# NanOSD.net
KiCad netlist of a schematic drawn in EAGLE
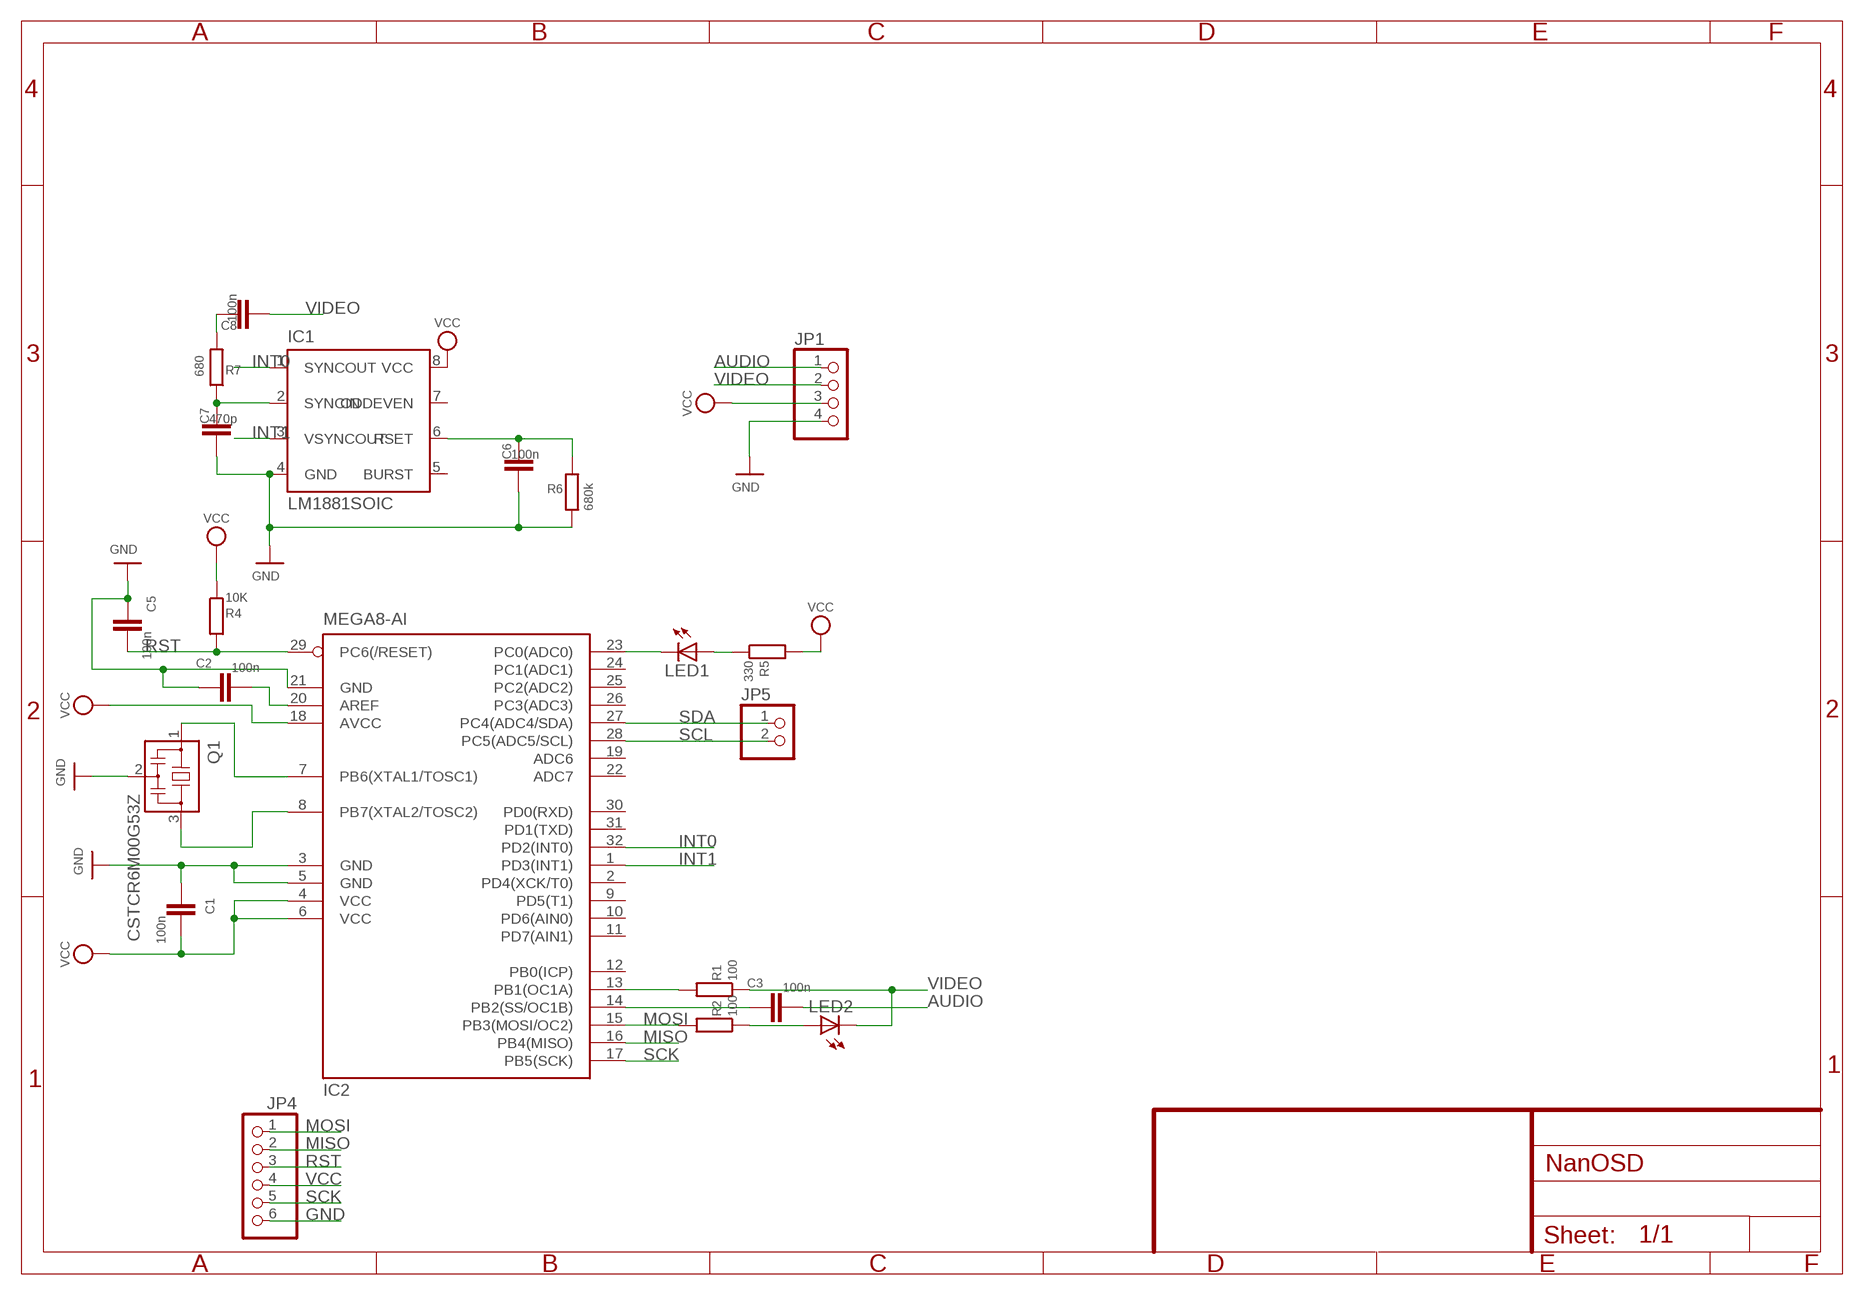
[diagram p0: schematic, sheet 1]

(export (version "E")
  (design (tool "Eeschema 10.0.6"))
  (components
    (comp (ref "C1")
      (value "100n")
      (footprint "eagle-import:C0805")
      (libsource (lib "eagle-import") (part "C-EUC0805"))
    )
    (comp (ref "C2")
      (value "100n")
      (footprint "eagle-import:C0805")
      (libsource (lib "eagle-import") (part "C-EUC0805"))
    )
    (comp (ref "C3")
      (value "100n")
      (footprint "eagle-import:C0805")
      (libsource (lib "eagle-import") (part "C-EUC0805"))
    )
    (comp (ref "C5")
      (value "100n")
      (footprint "eagle-import:C0805")
      (libsource (lib "eagle-import") (part "C-EUC0805"))
    )
    (comp (ref "C6")
      (value "100n")
      (footprint "eagle-import:C0805")
      (libsource (lib "eagle-import") (part "C-EUC0805"))
    )
    (comp (ref "C7")
      (value "470p")
      (footprint "eagle-import:C0805")
      (libsource (lib "eagle-import") (part "C-EUC0805"))
    )
    (comp (ref "C8")
      (value "100n")
      (footprint "eagle-import:C0805")
      (libsource (lib "eagle-import") (part "C-EUC0805"))
    )
    (comp (ref "IC1")
      (value "LM1881SOIC")
      (footprint "eagle-import:SO08")
      (libsource (lib "eagle-import") (part "LM1881SOIC"))
    )
    (comp (ref "IC2")
      (value "MEGA8-AI")
      (footprint "eagle-import:TQFP32-08")
      (fields (field (name "MPN") "ATMEGA8-16AU"))
      (libsource (lib "eagle-import") (part "MEGA8-AI"))
    )
    (comp (ref "JP1")
      (value "PINHD-1X4")
      (footprint "eagle-import:1X04")
      (libsource (lib "eagle-import") (part "PINHD-1X4"))
    )
    (comp (ref "JP4")
      (value "PINHD-1X61.27MM")
      (footprint "eagle-import:1X06")
      (libsource (lib "eagle-import") (part "PINHD-1X61.27MM"))
    )
    (comp (ref "JP5")
      (value "PINHD-1X2")
      (footprint "eagle-import:1X02")
      (libsource (lib "eagle-import") (part "PINHD-1X2"))
    )
    (comp (ref "LED1")
      (value "LEDCHIP-LED0805")
      (footprint "eagle-import:CHIP-LED0805")
      (libsource (lib "eagle-import") (part "LEDCHIP-LED0805"))
    )
    (comp (ref "LED2")
      (value "LEDCHIP-LED0805")
      (footprint "eagle-import:CHIP-LED0805")
      (libsource (lib "eagle-import") (part "LEDCHIP-LED0805"))
    )
    (comp (ref "Q1")
      (value "CSTCR6M00G53Z")
      (footprint "eagle-import:CSTCR6M")
      (fields (field (name "MPN") "CSTCR6M00G53-R0"))
      (libsource (lib "eagle-import") (part "CSTCR6M00G53Z"))
    )
    (comp (ref "R1")
      (value "100")
      (footprint "eagle-import:M0805")
      (libsource (lib "eagle-import") (part "R-EU_M0805"))
    )
    (comp (ref "R2")
      (value "100")
      (footprint "eagle-import:M0805")
      (libsource (lib "eagle-import") (part "R-EU_M0805"))
    )
    (comp (ref "R4")
      (value "10K")
      (footprint "eagle-import:M0805")
      (libsource (lib "eagle-import") (part "R-EU_M0805"))
    )
    (comp (ref "R5")
      (value "330")
      (footprint "eagle-import:M0805")
      (libsource (lib "eagle-import") (part "R-EU_M0805"))
    )
    (comp (ref "R6")
      (value "680k")
      (footprint "eagle-import:M0805")
      (libsource (lib "eagle-import") (part "R-EU_M0805"))
    )
    (comp (ref "R7")
      (value "680")
      (footprint "eagle-import:M0805")
      (libsource (lib "eagle-import") (part "R-EU_M0805"))
    )
  )
  (nets
    (net (code "1") (name "/AUDIO") (class "Default")
      (node (ref "C3") (pin "2") (pinfunction "2_2") (pintype "passive"))
      (node (ref "JP1") (pin "1") (pinfunction "1_1") (pintype "passive"))
    )
    (net (code "2") (name "/INT0") (class "Default")
      (node (ref "IC1") (pin "1") (pinfunction "SYNCOUT_1") (pintype "output"))
      (node (ref "IC2") (pin "32") (pinfunction "PD2(INT0)_32") (pintype "bidirectional"))
    )
    (net (code "3") (name "/INT1") (class "Default")
      (node (ref "IC1") (pin "3") (pinfunction "VSYNCOUT_3") (pintype "output"))
      (node (ref "IC2") (pin "1") (pinfunction "PD3(INT1)_1") (pintype "bidirectional"))
    )
    (net (code "4") (name "/MISO") (class "Default")
      (node (ref "IC2") (pin "16") (pinfunction "PB4(MISO)_16") (pintype "bidirectional"))
      (node (ref "JP4") (pin "2") (pinfunction "2_2") (pintype "passive"))
    )
    (net (code "5") (name "/MOSI") (class "Default")
      (node (ref "IC2") (pin "15") (pinfunction "PB3(MOSI/OC2)_15") (pintype "bidirectional"))
      (node (ref "JP4") (pin "1") (pinfunction "1_1") (pintype "passive"))
      (node (ref "R2") (pin "2") (pinfunction "2_2") (pintype "passive"))
    )
    (net (code "6") (name "/RST") (class "Default")
      (node (ref "C5") (pin "2") (pinfunction "2_2") (pintype "passive"))
      (node (ref "IC2") (pin "29") (pinfunction "PC6(/RESET)_29") (pintype "bidirectional"))
      (node (ref "JP4") (pin "3") (pinfunction "3_3") (pintype "passive"))
      (node (ref "R4") (pin "2") (pinfunction "2_2") (pintype "passive"))
    )
    (net (code "7") (name "/SCK") (class "Default")
      (node (ref "IC2") (pin "17") (pinfunction "PB5(SCK)_17") (pintype "bidirectional"))
      (node (ref "JP4") (pin "5") (pinfunction "5_5") (pintype "passive"))
    )
    (net (code "8") (name "/SCL") (class "Default")
      (node (ref "IC2") (pin "28") (pinfunction "PC5(ADC5/SCL)_28") (pintype "bidirectional"))
      (node (ref "JP5") (pin "2") (pinfunction "2_2") (pintype "passive"))
    )
    (net (code "9") (name "/SDA") (class "Default")
      (node (ref "IC2") (pin "27") (pinfunction "PC4(ADC4/SDA)_27") (pintype "bidirectional"))
      (node (ref "JP5") (pin "1") (pinfunction "1_1") (pintype "passive"))
    )
    (net (code "10") (name "/VIDEO") (class "Default")
      (node (ref "C8") (pin "1") (pinfunction "1_1") (pintype "passive"))
      (node (ref "JP1") (pin "2") (pinfunction "2_2") (pintype "passive"))
      (node (ref "LED2") (pin "C") (pinfunction "C_C") (pintype "passive"))
      (node (ref "R1") (pin "1") (pinfunction "1_1") (pintype "passive"))
    )
    (net (code "11") (name "GND") (class "Default")
      (node (ref "C1") (pin "1") (pinfunction "1_1") (pintype "passive"))
      (node (ref "C2") (pin "1") (pinfunction "1_1") (pintype "passive"))
      (node (ref "C5") (pin "1") (pinfunction "1_1") (pintype "passive"))
      (node (ref "C6") (pin "1") (pinfunction "1_1") (pintype "passive"))
      (node (ref "C7") (pin "1") (pinfunction "1_1") (pintype "passive"))
      (node (ref "IC1") (pin "4") (pinfunction "GND_4") (pintype "power_in"))
      (node (ref "IC2") (pin "21") (pinfunction "GND_21") (pintype "power_in"))
      (node (ref "IC2") (pin "3") (pinfunction "GND_3") (pintype "power_in"))
      (node (ref "IC2") (pin "5") (pinfunction "GND_5") (pintype "power_in"))
      (node (ref "JP1") (pin "4") (pinfunction "4_4") (pintype "passive"))
      (node (ref "JP4") (pin "6") (pinfunction "6_6") (pintype "passive"))
      (node (ref "Q1") (pin "2") (pinfunction "2_2") (pintype "passive"))
      (node (ref "R6") (pin "2") (pinfunction "2_2") (pintype "passive"))
    )
    (net (code "12") (name "Net-(C8-Pad2)") (class "Default")
      (node (ref "C8") (pin "2") (pinfunction "2_2") (pintype "passive"))
      (node (ref "R7") (pin "2") (pinfunction "2_2") (pintype "passive"))
    )
    (net (code "13") (name "Net-(IC1-RSET)") (class "Default")
      (node (ref "C6") (pin "2") (pinfunction "2_2") (pintype "passive"))
      (node (ref "IC1") (pin "6") (pinfunction "RSET_6") (pintype "output"))
      (node (ref "R6") (pin "1") (pinfunction "1_1") (pintype "passive"))
    )
    (net (code "14") (name "Net-(IC1-SYNCIN)") (class "Default")
      (node (ref "C7") (pin "2") (pinfunction "2_2") (pintype "passive"))
      (node (ref "IC1") (pin "2") (pinfunction "SYNCIN_2") (pintype "input"))
      (node (ref "R7") (pin "1") (pinfunction "1_1") (pintype "passive"))
    )
    (net (code "15") (name "Net-(IC2-AREF)") (class "Default")
      (node (ref "C2") (pin "2") (pinfunction "2_2") (pintype "passive"))
      (node (ref "IC2") (pin "20") (pinfunction "AREF_20") (pintype "passive"))
    )
    (net (code "16") (name "Net-(IC2-PB1(OC1A))") (class "Default")
      (node (ref "IC2") (pin "13") (pinfunction "PB1(OC1A)_13") (pintype "bidirectional"))
      (node (ref "R1") (pin "2") (pinfunction "2_2") (pintype "passive"))
    )
    (net (code "17") (name "Net-(IC2-PB2(SS{slash}OC1B))") (class "Default")
      (node (ref "C3") (pin "1") (pinfunction "1_1") (pintype "passive"))
      (node (ref "IC2") (pin "14") (pinfunction "PB2(SS/OC1B)_14") (pintype "bidirectional"))
    )
    (net (code "18") (name "Net-(IC2-PB6(XTAL1{slash}TOSC1))") (class "Default")
      (node (ref "IC2") (pin "7") (pinfunction "PB6(XTAL1/TOSC1)_7") (pintype "bidirectional"))
      (node (ref "Q1") (pin "1") (pinfunction "1_1") (pintype "passive"))
    )
    (net (code "19") (name "Net-(IC2-PB7(XTAL2{slash}TOSC2))") (class "Default")
      (node (ref "IC2") (pin "8") (pinfunction "PB7(XTAL2/TOSC2)_8") (pintype "bidirectional"))
      (node (ref "Q1") (pin "3") (pinfunction "3_3") (pintype "passive"))
    )
    (net (code "20") (name "Net-(IC2-PC0(ADC0))") (class "Default")
      (node (ref "IC2") (pin "23") (pinfunction "PC0(ADC0)_23") (pintype "bidirectional"))
      (node (ref "LED1") (pin "C") (pinfunction "C_C") (pintype "passive"))
    )
    (net (code "21") (name "Net-(LED1-PadA)") (class "Default")
      (node (ref "LED1") (pin "A") (pinfunction "A_A") (pintype "passive"))
      (node (ref "R5") (pin "1") (pinfunction "1_1") (pintype "passive"))
    )
    (net (code "22") (name "Net-(LED2-PadA)") (class "Default")
      (node (ref "LED2") (pin "A") (pinfunction "A_A") (pintype "passive"))
      (node (ref "R2") (pin "1") (pinfunction "1_1") (pintype "passive"))
    )
    (net (code "23") (name "VCC") (class "Default")
      (node (ref "C1") (pin "2") (pinfunction "2_2") (pintype "passive"))
      (node (ref "IC1") (pin "8") (pinfunction "VCC_8") (pintype "power_in"))
      (node (ref "IC2") (pin "18") (pinfunction "AVCC_18") (pintype "power_in"))
      (node (ref "IC2") (pin "4") (pinfunction "VCC_4") (pintype "power_in"))
      (node (ref "IC2") (pin "6") (pinfunction "VCC_6") (pintype "power_in"))
      (node (ref "JP1") (pin "3") (pinfunction "3_3") (pintype "passive"))
      (node (ref "JP4") (pin "4") (pinfunction "4_4") (pintype "passive"))
      (node (ref "R4") (pin "1") (pinfunction "1_1") (pintype "passive"))
      (node (ref "R5") (pin "2") (pinfunction "2_2") (pintype "passive"))
    )
    (net (code "24") (name "unconnected-(IC1-BURST-Pad5)") (class "Default")
      (node (ref "IC1") (pin "5") (pinfunction "BURST_5") (pintype "output"))
    )
    (net (code "25") (name "unconnected-(IC1-ODDEVEN-Pad7)") (class "Default")
      (node (ref "IC1") (pin "7") (pinfunction "ODDEVEN_7") (pintype "output"))
    )
    (net (code "26") (name "unconnected-(IC2-ADC6-Pad19)") (class "Default")
      (node (ref "IC2") (pin "19") (pinfunction "ADC6_19") (pintype "bidirectional"))
    )
    (net (code "27") (name "unconnected-(IC2-ADC7-Pad22)") (class "Default")
      (node (ref "IC2") (pin "22") (pinfunction "ADC7_22") (pintype "bidirectional"))
    )
    (net (code "28") (name "unconnected-(IC2-PB0(ICP)-Pad12)") (class "Default")
      (node (ref "IC2") (pin "12") (pinfunction "PB0(ICP)_12") (pintype "bidirectional"))
    )
    (net (code "29") (name "unconnected-(IC2-PC1(ADC1)-Pad24)") (class "Default")
      (node (ref "IC2") (pin "24") (pinfunction "PC1(ADC1)_24") (pintype "bidirectional"))
    )
    (net (code "30") (name "unconnected-(IC2-PC2(ADC2)-Pad25)") (class "Default")
      (node (ref "IC2") (pin "25") (pinfunction "PC2(ADC2)_25") (pintype "bidirectional"))
    )
    (net (code "31") (name "unconnected-(IC2-PC3(ADC3)-Pad26)") (class "Default")
      (node (ref "IC2") (pin "26") (pinfunction "PC3(ADC3)_26") (pintype "bidirectional"))
    )
    (net (code "32") (name "unconnected-(IC2-PD0(RXD)-Pad30)") (class "Default")
      (node (ref "IC2") (pin "30") (pinfunction "PD0(RXD)_30") (pintype "bidirectional"))
    )
    (net (code "33") (name "unconnected-(IC2-PD1(TXD)-Pad31)") (class "Default")
      (node (ref "IC2") (pin "31") (pinfunction "PD1(TXD)_31") (pintype "bidirectional"))
    )
    (net (code "34") (name "unconnected-(IC2-PD4(XCK{slash}T0)-Pad2)") (class "Default")
      (node (ref "IC2") (pin "2") (pinfunction "PD4(XCK/T0)_2") (pintype "bidirectional"))
    )
    (net (code "35") (name "unconnected-(IC2-PD5(T1)-Pad9)") (class "Default")
      (node (ref "IC2") (pin "9") (pinfunction "PD5(T1)_9") (pintype "bidirectional"))
    )
    (net (code "36") (name "unconnected-(IC2-PD6(AIN0)-Pad10)") (class "Default")
      (node (ref "IC2") (pin "10") (pinfunction "PD6(AIN0)_10") (pintype "bidirectional"))
    )
    (net (code "37") (name "unconnected-(IC2-PD7(AIN1)-Pad11)") (class "Default")
      (node (ref "IC2") (pin "11") (pinfunction "PD7(AIN1)_11") (pintype "bidirectional"))
    )
  )
)
